# POWER.net
KiCad netlist of a schematic drawn in Altium Designer
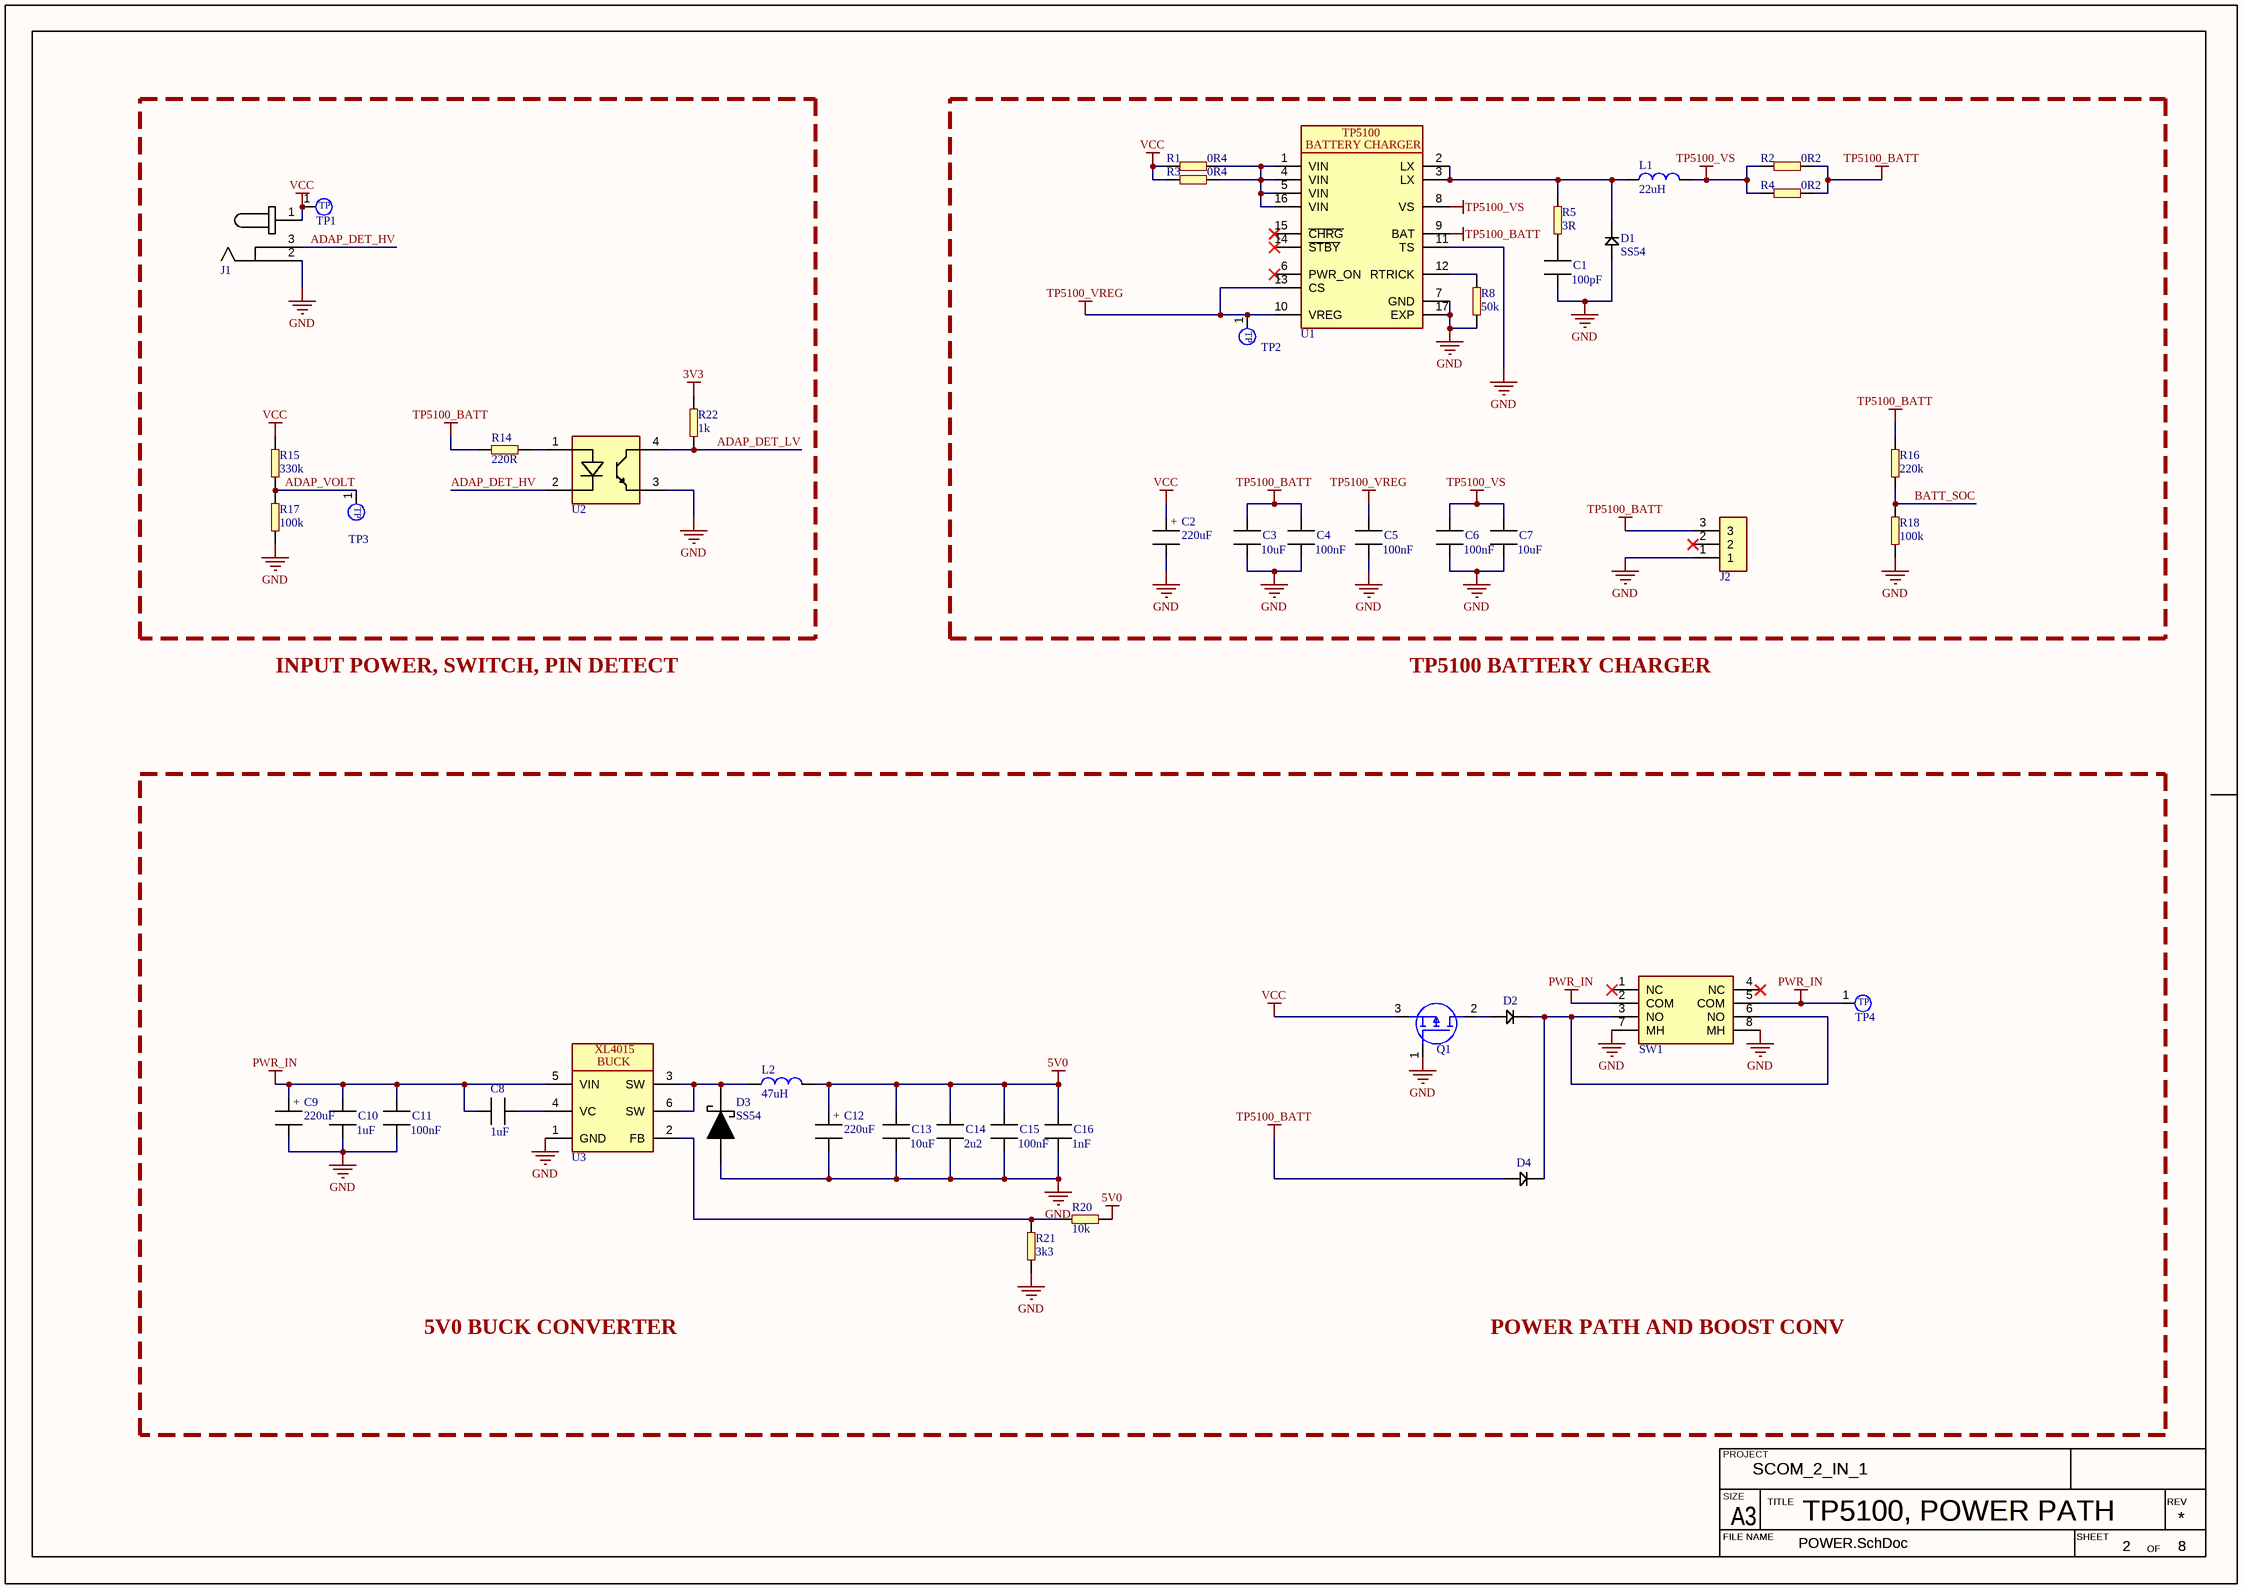
[diagram p0: POWER.SchDoc]

(export (version "E")
  (design (tool "Eeschema 10.0.6"))
  (components
    (comp (ref "C1")
      (value "100pF")
      (footprint "CAPC2012X13L")
      (description "Chip Capacitor, 2-Leads, Body 2.00x1.25mm, IPC High Density")
      (fields (field (name "Comment") "MLCC_0805"))
      (libsource (lib "Capacitor") (part "MLCC_0805"))
    )
    (comp (ref "C2")
      (value "220uF")
      (footprint "CAP_D10_H16_P5")
      (description "Electrolytic Capacitor Through Hole D10 P5.0")
      (fields (field (name "Comment") "ERP_102-2"))
      (libsource (lib "ElectrolyticCapacitor") (part "CAP_D10_H16_P5"))
    )
    (comp (ref "C3")
      (value "10uF")
      (footprint "CAPC2012X13L")
      (description "1uF 105 0805 (2012 metric) 50V X7R MLCC SMD")
      (fields (field (name "Comment") "MLCC_0805"))
      (libsource (lib "Capacitor") (part "MLCC_0805"))
    )
    (comp (ref "C4")
      (value "100nF")
      (footprint "CAPC2012X13L")
      (description "1uF 105 0805 (2012 metric) 50V X7R MLCC SMD")
      (fields (field (name "Comment") "MLCC_0805"))
      (libsource (lib "Capacitor") (part "MLCC_0805"))
    )
    (comp (ref "C5")
      (value "100nF")
      (footprint "CAPC2012X13L")
      (description "1uF 105 0805 (2012 metric) 50V X7R MLCC SMD")
      (fields (field (name "Comment") "MLCC_0805"))
      (libsource (lib "Capacitor") (part "MLCC_0805"))
    )
    (comp (ref "C6")
      (value "100nF")
      (footprint "CAPC2012X13L")
      (description "1uF 105 0805 (2012 metric) 50V X7R MLCC SMD")
      (fields (field (name "Comment") "MLCC_0805"))
      (libsource (lib "Capacitor") (part "MLCC_0805"))
    )
    (comp (ref "C7")
      (value "10uF")
      (footprint "CAPC2012X13L")
      (description "1uF 105 0805 (2012 metric) 50V X7R MLCC SMD")
      (fields (field (name "Comment") "MLCC_0805"))
      (libsource (lib "Capacitor") (part "MLCC_0805"))
    )
    (comp (ref "C8")
      (value "1uF")
      (footprint "CAPC2012X13L")
      (description "1uF 105 0805 (2012 metric) 50V X7R MLCC SMD")
      (fields (field (name "Comment") "MLCC_0805"))
      (libsource (lib "Capacitor") (part "MLCC_0805"))
    )
    (comp (ref "C9")
      (value "220uF")
      (footprint "CAP_D10_H16_P5")
      (description "Electrolytic Capacitor Through Hole D10 P5.0")
      (fields (field (name "Comment") "ERP_102-2"))
      (libsource (lib "ElectrolyticCapacitor") (part "CAP_D10_H16_P5"))
    )
    (comp (ref "C10")
      (value "1uF")
      (footprint "CAPC2012X13L")
      (description "1uF 105 0805 (2012 metric) 50V X7R MLCC SMD")
      (fields (field (name "Comment") "MLCC_0805"))
      (libsource (lib "Capacitor") (part "MLCC_0805"))
    )
    (comp (ref "C11")
      (value "100nF")
      (footprint "CAPC2012X13L")
      (description "Chip Capacitor, 2-Leads, Body 2.00x1.25mm, IPC High Density")
      (fields (field (name "Comment") "MLCC_0805"))
      (libsource (lib "Capacitor") (part "MLCC_0805"))
    )
    (comp (ref "C12")
      (value "220uF")
      (footprint "CAP_D10_H16_P5")
      (description "Electrolytic Capacitor Through Hole D10 P5.0")
      (fields (field (name "Comment") "ERP_102-2"))
      (libsource (lib "ElectrolyticCapacitor") (part "CAP_D10_H16_P5"))
    )
    (comp (ref "C13")
      (value "10uF")
      (footprint "CAPC2012X13L")
      (description "1uF 105 0805 (2012 metric) 50V X7R MLCC SMD")
      (fields (field (name "Comment") "MLCC_0805"))
      (libsource (lib "Capacitor") (part "MLCC_0805"))
    )
    (comp (ref "C14")
      (value "2u2")
      (footprint "CAPC2012X13L")
      (description "Chip Capacitor, 2-Leads, Body 2.00x1.25mm, IPC High Density")
      (fields (field (name "Comment") "MLCC_0805"))
      (libsource (lib "Capacitor") (part "MLCC_0805"))
    )
    (comp (ref "C15")
      (value "100nF")
      (footprint "CAPC2012X13L")
      (description "Chip Capacitor, 2-Leads, Body 2.00x1.25mm, IPC High Density")
      (fields (field (name "Comment") "MLCC_0805"))
      (libsource (lib "Capacitor") (part "MLCC_0805"))
    )
    (comp (ref "C16")
      (value "1nF")
      (footprint "CAPC2012X13L")
      (description "Chip Capacitor, 2-Leads, Body 2.00x1.25mm, IPC High Density")
      (fields (field (name "Comment") "MLCC_0805"))
      (libsource (lib "Capacitor") (part "MLCC_0805"))
    )
    (comp (ref "D1")
      (value "SS54")
      (footprint "DIOM6959X26L")
      (fields (field (name "Comment") "ERP_104-3"))
      (libsource (lib "") (part "SS54_1"))
    )
    (comp (ref "D2") (value "ERP_104-3") (footprint "DIOM6959X26L") (libsource (lib "") (part "SS54_1")))
    (comp (ref "D3")
      (value "SS54")
      (footprint "DIOM6959X26L")
      (fields (field (name "Comment") "ERP_104-3"))
      (libsource (lib "Schottky") (part "SS54"))
    )
    (comp (ref "D4") (value "ERP_104-3") (footprint "DIOM6959X26L") (libsource (lib "") (part "SS54_1")))
    (comp (ref "J1")
      (value "KLDX-0202-AC")
      (footprint "KLDX-0202-AC")
      (description "CONN PWR JACK 2X5.5MM KINKED PIN")
      (libsource (lib "Connectors") (part "KLDX-0202-AC"))
    )
    (comp (ref "J2")
      (value "Molex_5.08_3P")
      (footprint "Molex_5.08_3P")
      (description "Molex 7A 5.08mm Connector 3 Pin")
      (libsource (lib "Connectors") (part "Molex_5.08_3P"))
    )
    (comp (ref "L1")
      (value "22uH")
      (footprint "IND_1212")
      (description "IND_1212")
      (libsource (lib "") (part "IND_1212_1"))
    )
    (comp (ref "L2")
      (value "47uH")
      (footprint "IND_1212")
      (description "IND_1212")
      (fields (field (name "Comment") "ERP_103-3"))
      (libsource (lib "Inductor") (part "IND_1212"))
    )
    (comp (ref "Q1")
      (value "IRFR5305TRPBF")
      (footprint "DPAK229P991X239-3M")
      (description "P Channel MOSFET -55V HEXFET 65mOhms 42nC TO-252-3")
      (libsource (lib "MOSFET") (part "IRFR5305TRPBF"))
    )
    (comp (ref "R1")
      (value "0R4")
      (footprint "RESC3116X06M")
      (description "RES_1206")
      (libsource (lib "Resistor") (part "RES_1206"))
    )
    (comp (ref "R2")
      (value "0R2")
      (footprint "RESC3116X06M")
      (description "RES_1206")
      (libsource (lib "Resistor") (part "RES_1206"))
    )
    (comp (ref "R3")
      (value "0R4")
      (footprint "RESC3116X06M")
      (description "RES_1206")
      (libsource (lib "Resistor") (part "RES_1206"))
    )
    (comp (ref "R4")
      (value "0R2")
      (footprint "RESC3116X06M")
      (description "RES_1206")
      (libsource (lib "Resistor") (part "RES_1206"))
    )
    (comp (ref "R5")
      (value "3R")
      (footprint "RES_0603")
      (description "RES_0603")
      (fields (field (name "Comment") "ERP_101-1"))
      (libsource (lib "") (part "RES_0603_1"))
    )
    (comp (ref "R8")
      (value "50k")
      (footprint "RES_0603")
      (description "RES_0603")
      (fields (field (name "Comment") "ERP_101-1"))
      (libsource (lib "") (part "RES_0603_1"))
    )
    (comp (ref "R14")
      (value "220R")
      (footprint "RES_0603")
      (description "RES_0603")
      (fields (field (name "Comment") "ERP_101-1"))
      (libsource (lib "") (part "RES_0603_3"))
    )
    (comp (ref "R15")
      (value "330k")
      (footprint "RES_0603")
      (description "RES_0603")
      (fields (field (name "Comment") "ERP_101-1"))
      (libsource (lib "") (part "RES_0603_1"))
    )
    (comp (ref "R16")
      (value "220k")
      (footprint "RES_0603")
      (description "RES_0603")
      (fields (field (name "Comment") "ERP_101-1"))
      (libsource (lib "") (part "RES_0603_1"))
    )
    (comp (ref "R17")
      (value "100k")
      (footprint "RES_0603")
      (description "RES_0603")
      (fields (field (name "Comment") "ERP_101-1"))
      (libsource (lib "Resistor") (part "RES_0603"))
    )
    (comp (ref "R18")
      (value "100k")
      (footprint "RES_0603")
      (description "RES_0603")
      (fields (field (name "Comment") "ERP_101-1"))
      (libsource (lib "") (part "RES_0603_1"))
    )
    (comp (ref "R20")
      (value "10k")
      (footprint "RES_0603")
      (description "RES_0603")
      (fields (field (name "Comment") "ERP_101-1"))
      (libsource (lib "") (part "RES_0603_2"))
    )
    (comp (ref "R21")
      (value "3k3")
      (footprint "RES_0603")
      (description "RES_0603")
      (fields (field (name "Comment") "ERP_101-1"))
      (libsource (lib "Resistor") (part "RES_0603"))
    )
    (comp (ref "R22")
      (value "1k")
      (footprint "RES_0603")
      (description "RES_0603")
      (fields (field (name "Comment") "ERP_101-1"))
      (libsource (lib "") (part "RES_0603_1"))
    )
    (comp (ref "SW1")
      (value "ERP_110-4")
      (footprint "PBH2U")
      (description "Pushbutton Switch DPDT Standard Through Hole, Right Angle")
      (libsource (lib "Switch") (part "PBH2U"))
    )
    (comp (ref "TP1") (value "TP_1MM") (footprint "TP_1MM") (libsource (lib "Jumper") (part "TP_1MM")))
    (comp (ref "TP2") (value "TP_1MM") (footprint "TP_1MM") (libsource (lib "Jumper") (part "TP_1MM")))
    (comp (ref "TP3") (value "TP_1MM") (footprint "TP_1MM") (libsource (lib "Jumper") (part "TP_1MM")))
    (comp (ref "TP4") (value "TP_1MM") (footprint "TP_1MM") (libsource (lib "Jumper") (part "TP_1MM")))
    (comp (ref "U1")
      (value "TP5100")
      (footprint "QFN65P400X400X90_HS-17M")
      (description "Switching-buck type (double 8.4V / single 4.2V) lithium battery charging management chip")
      (libsource (lib "BatteryCharger") (part "TP5100"))
    )
    (comp (ref "U2")
      (value "FOD817A3SD")
      (footprint "FOD817A3SD")
      (description "OPTOISOLATOR 5KV TRANSISTOR 4SMD")
      (libsource (lib "Optocoupler") (part "FOD817A3SD"))
    )
    (comp (ref "U3")
      (value "XL4015")
      (footprint "XL4015")
      (description "5A 180KHz 36V Buck DC to DC Converter")
      (libsource (lib "DCDC_Switcher") (part "XL4015"))
    )
  )
  (nets
    (net (code "1") (name "/ADAP_DET_HV") (class "Default")
      (node (ref "J1") (pin "3") (pinfunction "3_3") (pintype "passive"))
      (node (ref "U2") (pin "2") (pinfunction "CATHODE_2") (pintype "passive"))
    )
    (net (code "2") (name "/ADAP_DET_LV") (class "Default")
      (node (ref "R22") (pin "1") (pinfunction "1_1") (pintype "passive"))
      (node (ref "U2") (pin "4") (pinfunction "COLLECTOR_4") (pintype "passive"))
    )
    (net (code "3") (name "/ADAP_VOLT") (class "Default")
      (node (ref "R15") (pin "1") (pinfunction "1_1") (pintype "passive"))
      (node (ref "R17") (pin "1") (pinfunction "1_1") (pintype "passive"))
      (node (ref "TP3") (pin "1") (pinfunction "1_1") (pintype "passive"))
    )
    (net (code "4") (name "/BATT_SOC") (class "Default")
      (node (ref "R16") (pin "1") (pinfunction "1_1") (pintype "passive"))
      (node (ref "R18") (pin "2") (pinfunction "2_2") (pintype "passive"))
    )
    (net (code "5") (name "3V3") (class "Default")
      (node (ref "R22") (pin "2") (pinfunction "2_2") (pintype "passive"))
    )
    (net (code "6") (name "5V0") (class "Default")
      (node (ref "C12") (pin "1") (pinfunction "1_1") (pintype "passive"))
      (node (ref "C13") (pin "1") (pinfunction "1_1") (pintype "passive"))
      (node (ref "C14") (pin "1") (pinfunction "1_1") (pintype "passive"))
      (node (ref "C15") (pin "1") (pinfunction "1_1") (pintype "passive"))
      (node (ref "C16") (pin "1") (pinfunction "1_1") (pintype "passive"))
      (node (ref "L2") (pin "1") (pinfunction "1_1") (pintype "passive"))
      (node (ref "R20") (pin "1") (pinfunction "1_1") (pintype "passive"))
    )
    (net (code "7") (name "GND") (class "Default")
      (node (ref "C1") (pin "2") (pinfunction "2_2") (pintype "passive"))
      (node (ref "C10") (pin "2") (pinfunction "2_2") (pintype "passive"))
      (node (ref "C11") (pin "2") (pinfunction "2_2") (pintype "passive"))
      (node (ref "C12") (pin "2") (pinfunction "2_2") (pintype "passive"))
      (node (ref "C13") (pin "2") (pinfunction "2_2") (pintype "passive"))
      (node (ref "C14") (pin "2") (pinfunction "2_2") (pintype "passive"))
      (node (ref "C15") (pin "2") (pinfunction "2_2") (pintype "passive"))
      (node (ref "C16") (pin "2") (pinfunction "2_2") (pintype "passive"))
      (node (ref "C2") (pin "2") (pinfunction "2_2") (pintype "passive"))
      (node (ref "C3") (pin "2") (pinfunction "2_2") (pintype "passive"))
      (node (ref "C4") (pin "2") (pinfunction "2_2") (pintype "passive"))
      (node (ref "C5") (pin "2") (pinfunction "2_2") (pintype "passive"))
      (node (ref "C6") (pin "2") (pinfunction "2_2") (pintype "passive"))
      (node (ref "C7") (pin "2") (pinfunction "2_2") (pintype "passive"))
      (node (ref "C9") (pin "2") (pinfunction "2_2") (pintype "passive"))
      (node (ref "D1") (pin "2") (pinfunction "A_2") (pintype "passive"))
      (node (ref "D3") (pin "2") (pinfunction "A_2") (pintype "passive"))
      (node (ref "J1") (pin "2") (pinfunction "2_2") (pintype "passive"))
      (node (ref "J2") (pin "1") (pinfunction "1_1") (pintype "passive"))
      (node (ref "Q1") (pin "1") (pinfunction "G_1") (pintype "passive"))
      (node (ref "R17") (pin "2") (pinfunction "2_2") (pintype "passive"))
      (node (ref "R18") (pin "1") (pinfunction "1_1") (pintype "passive"))
      (node (ref "R21") (pin "2") (pinfunction "2_2") (pintype "passive"))
      (node (ref "R8") (pin "1") (pinfunction "1_1") (pintype "passive"))
      (node (ref "SW1") (pin "7") (pinfunction "MH_7") (pintype "passive"))
      (node (ref "SW1") (pin "8") (pinfunction "MH_8") (pintype "passive"))
      (node (ref "U1") (pin "11") (pinfunction "TS_11") (pintype "passive"))
      (node (ref "U1") (pin "17") (pinfunction "EXP_17") (pintype "passive"))
      (node (ref "U1") (pin "7") (pinfunction "GND_7") (pintype "passive"))
      (node (ref "U2") (pin "3") (pinfunction "EMITTER_3") (pintype "passive"))
      (node (ref "U3") (pin "1") (pinfunction "GND_1") (pintype "passive"))
    )
    (net (code "8") (name "Net-(C1-Pad1)") (class "Default")
      (node (ref "C1") (pin "1") (pinfunction "1_1") (pintype "passive"))
      (node (ref "R5") (pin "1") (pinfunction "1_1") (pintype "passive"))
    )
    (net (code "9") (name "Net-(D1-C)") (class "Default")
      (node (ref "D1") (pin "1") (pinfunction "C_1") (pintype "passive"))
      (node (ref "L1") (pin "1") (pinfunction "1_1") (pintype "passive"))
      (node (ref "R5") (pin "2") (pinfunction "2_2") (pintype "passive"))
      (node (ref "U1") (pin "2") (pinfunction "LX_2") (pintype "passive"))
      (node (ref "U1") (pin "3") (pinfunction "LX_3") (pintype "passive"))
    )
    (net (code "10") (name "Net-(D2-A)") (class "Default")
      (node (ref "D2") (pin "2") (pinfunction "A_2") (pintype "passive"))
      (node (ref "Q1") (pin "2") (pinfunction "D_2") (pintype "passive"))
    )
    (net (code "11") (name "Net-(D2-C)") (class "Default")
      (node (ref "D2") (pin "1") (pinfunction "C_1") (pintype "passive"))
      (node (ref "D4") (pin "1") (pinfunction "C_1") (pintype "passive"))
      (node (ref "SW1") (pin "3") (pinfunction "NO_3") (pintype "passive"))
      (node (ref "SW1") (pin "6") (pinfunction "NO_6") (pintype "passive"))
    )
    (net (code "12") (name "Net-(D3-C)") (class "Default")
      (node (ref "D3") (pin "1") (pinfunction "C_1") (pintype "passive"))
      (node (ref "L2") (pin "2") (pinfunction "2_2") (pintype "passive"))
      (node (ref "U3") (pin "3") (pinfunction "SW_3") (pintype "passive"))
      (node (ref "U3") (pin "6") (pinfunction "SW_6") (pintype "passive"))
    )
    (net (code "13") (name "Net-(R1-Pad1)") (class "Default")
      (node (ref "R1") (pin "1") (pinfunction "1_1") (pintype "passive"))
      (node (ref "R3") (pin "1") (pinfunction "1_1") (pintype "passive"))
      (node (ref "U1") (pin "1") (pinfunction "VIN_1") (pintype "passive"))
      (node (ref "U1") (pin "16") (pinfunction "VIN_16") (pintype "passive"))
      (node (ref "U1") (pin "4") (pinfunction "VIN_4") (pintype "passive"))
      (node (ref "U1") (pin "5") (pinfunction "VIN_5") (pintype "passive"))
    )
    (net (code "14") (name "Net-(U1-RTRICK)") (class "Default")
      (node (ref "R8") (pin "2") (pinfunction "2_2") (pintype "passive"))
      (node (ref "U1") (pin "12") (pinfunction "RTRICK_12") (pintype "passive"))
    )
    (net (code "15") (name "Net-(U2-ANODE)") (class "Default")
      (node (ref "R14") (pin "2") (pinfunction "2_2") (pintype "passive"))
      (node (ref "U2") (pin "1") (pinfunction "ANODE_1") (pintype "passive"))
    )
    (net (code "16") (name "Net-(U3-FB)") (class "Default")
      (node (ref "R20") (pin "2") (pinfunction "2_2") (pintype "passive"))
      (node (ref "R21") (pin "1") (pinfunction "1_1") (pintype "passive"))
      (node (ref "U3") (pin "2") (pinfunction "FB_2") (pintype "passive"))
    )
    (net (code "17") (name "Net-(U3-VC)") (class "Default")
      (node (ref "C8") (pin "2") (pinfunction "2_2") (pintype "passive"))
      (node (ref "U3") (pin "4") (pinfunction "VC_4") (pintype "passive"))
    )
    (net (code "18") (name "PWR_IN") (class "Default")
      (node (ref "C10") (pin "1") (pinfunction "1_1") (pintype "passive"))
      (node (ref "C11") (pin "1") (pinfunction "1_1") (pintype "passive"))
      (node (ref "C8") (pin "1") (pinfunction "1_1") (pintype "passive"))
      (node (ref "C9") (pin "1") (pinfunction "1_1") (pintype "passive"))
      (node (ref "SW1") (pin "2") (pinfunction "COM_2") (pintype "passive"))
      (node (ref "SW1") (pin "5") (pinfunction "COM_5") (pintype "passive"))
      (node (ref "TP4") (pin "1") (pinfunction "1_1") (pintype "passive"))
      (node (ref "U3") (pin "5") (pinfunction "VIN_5") (pintype "passive"))
    )
    (net (code "19") (name "TP5100_BATT") (class "Default")
      (node (ref "C3") (pin "1") (pinfunction "1_1") (pintype "passive"))
      (node (ref "C4") (pin "1") (pinfunction "1_1") (pintype "passive"))
      (node (ref "D4") (pin "2") (pinfunction "A_2") (pintype "passive"))
      (node (ref "J2") (pin "3") (pinfunction "3_3") (pintype "passive"))
      (node (ref "R14") (pin "1") (pinfunction "1_1") (pintype "passive"))
      (node (ref "R16") (pin "2") (pinfunction "2_2") (pintype "passive"))
      (node (ref "R2") (pin "1") (pinfunction "1_1") (pintype "passive"))
      (node (ref "R4") (pin "1") (pinfunction "1_1") (pintype "passive"))
      (node (ref "U1") (pin "9") (pinfunction "BAT_9") (pintype "passive"))
    )
    (net (code "20") (name "TP5100_VREG") (class "Default")
      (node (ref "C5") (pin "1") (pinfunction "1_1") (pintype "passive"))
      (node (ref "TP2") (pin "1") (pinfunction "1_1") (pintype "passive"))
      (node (ref "U1") (pin "10") (pinfunction "VREG_10") (pintype "passive"))
      (node (ref "U1") (pin "13") (pinfunction "CS_13") (pintype "passive"))
    )
    (net (code "21") (name "TP5100_VS") (class "Default")
      (node (ref "C6") (pin "1") (pinfunction "1_1") (pintype "passive"))
      (node (ref "C7") (pin "1") (pinfunction "1_1") (pintype "passive"))
      (node (ref "L1") (pin "2") (pinfunction "2_2") (pintype "passive"))
      (node (ref "R2") (pin "2") (pinfunction "2_2") (pintype "passive"))
      (node (ref "R4") (pin "2") (pinfunction "2_2") (pintype "passive"))
      (node (ref "U1") (pin "8") (pinfunction "VS_8") (pintype "passive"))
    )
    (net (code "22") (name "VCC") (class "Default")
      (node (ref "C2") (pin "1") (pinfunction "1_1") (pintype "passive"))
      (node (ref "J1") (pin "1") (pinfunction "1_1") (pintype "passive"))
      (node (ref "Q1") (pin "3") (pinfunction "S_3") (pintype "passive"))
      (node (ref "R1") (pin "2") (pinfunction "2_2") (pintype "passive"))
      (node (ref "R15") (pin "2") (pinfunction "2_2") (pintype "passive"))
      (node (ref "R3") (pin "2") (pinfunction "2_2") (pintype "passive"))
      (node (ref "TP1") (pin "1") (pinfunction "1_1") (pintype "passive"))
    )
    (net (code "23") (name "unconnected-(J2-Pad2)") (class "Default")
      (node (ref "J2") (pin "2") (pinfunction "2_2") (pintype "passive+no_connect"))
    )
    (net (code "24") (name "unconnected-(SW1-NC-Pad1)") (class "Default")
      (node (ref "SW1") (pin "1") (pinfunction "NC_1") (pintype "passive+no_connect"))
    )
    (net (code "25") (name "unconnected-(SW1-NC-Pad4)") (class "Default")
      (node (ref "SW1") (pin "4") (pinfunction "NC_4") (pintype "passive+no_connect"))
    )
    (net (code "26") (name "unconnected-(U1-PWR_ON-Pad6)") (class "Default")
      (node (ref "U1") (pin "6") (pinfunction "PWR_ON_6") (pintype "passive+no_connect"))
    )
    (net (code "27") (name "unconnected-(U1-~{CHRG}-Pad15)") (class "Default")
      (node (ref "U1") (pin "15") (pinfunction "~{CHRG}_15") (pintype "passive+no_connect"))
    )
    (net (code "28") (name "unconnected-(U1-~{STBY}-Pad14)") (class "Default")
      (node (ref "U1") (pin "14") (pinfunction "~{STBY}_14") (pintype "passive+no_connect"))
    )
  )
)
